# yamaHACK.net
KiCad netlist of a schematic drawn in EAGLE
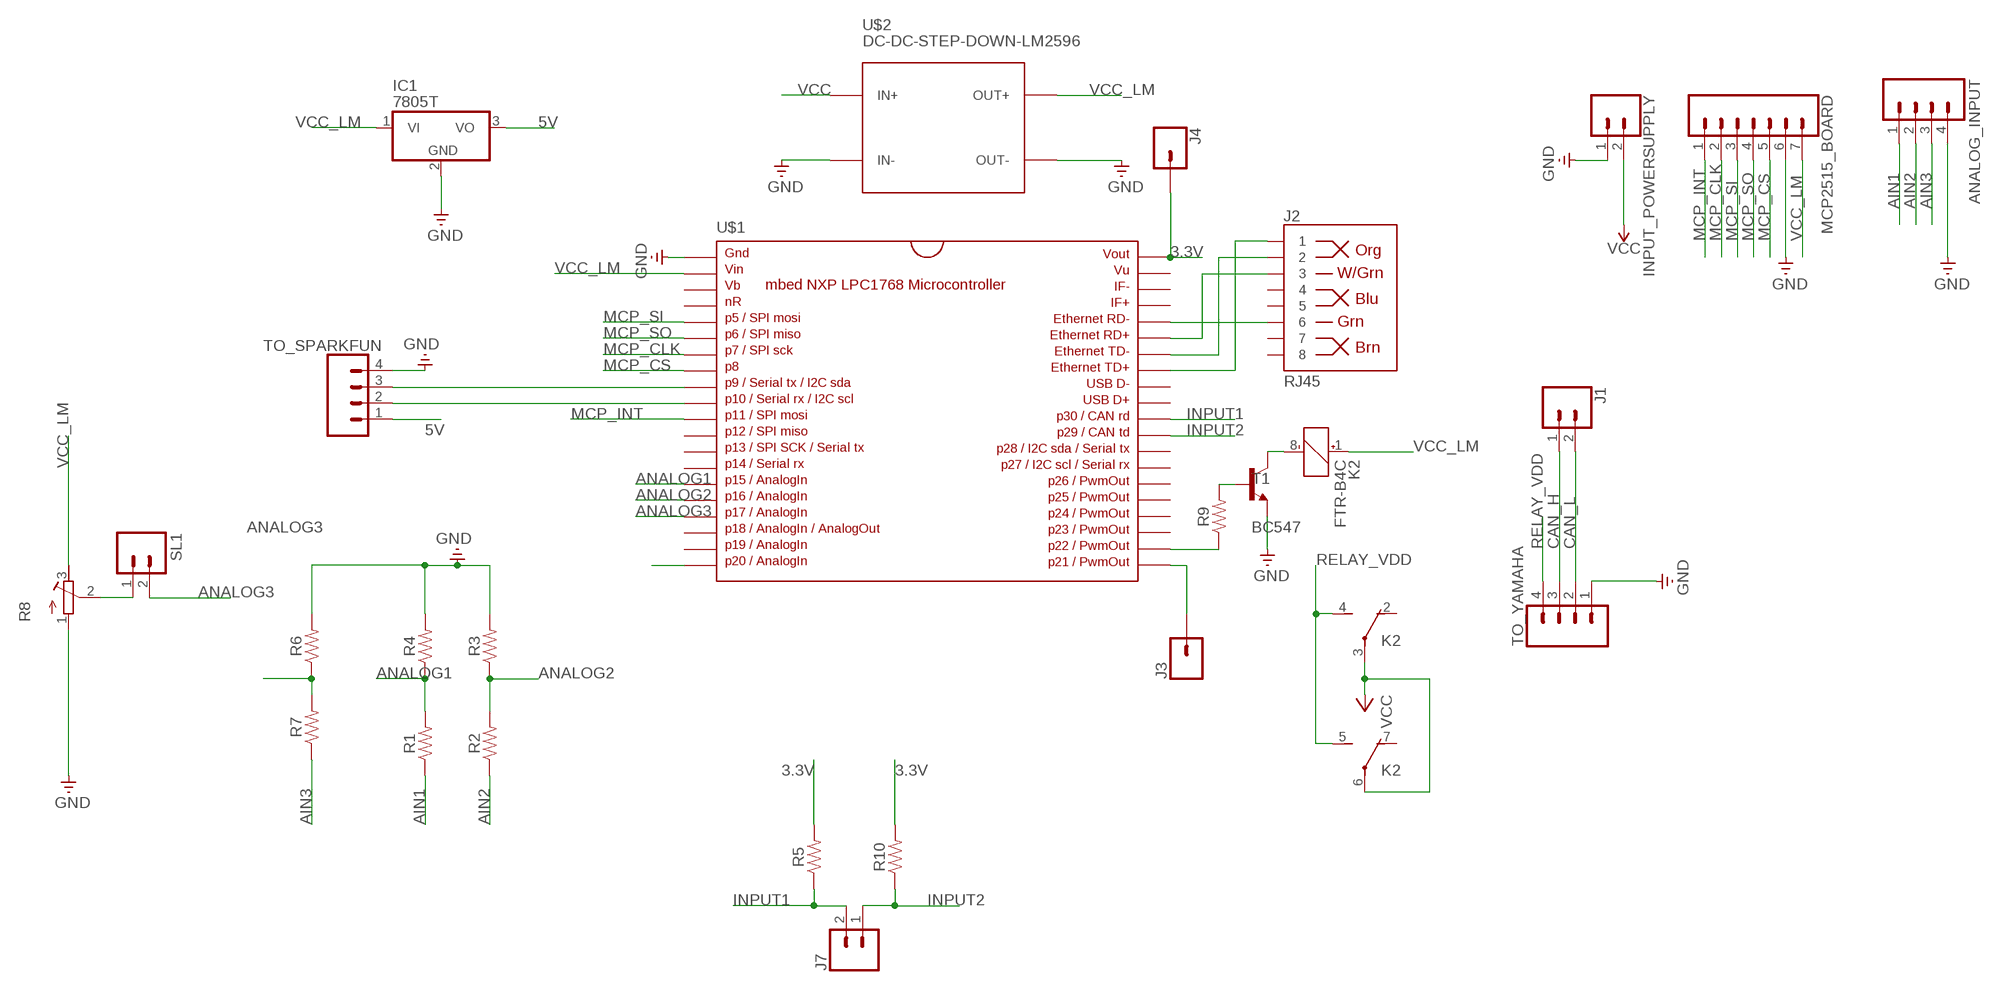
[diagram p0: schematic, sheet 1]

(export (version "E")
  (design (tool "Eeschema 10.0.6"))
  (components
    (comp (ref "ANALOG_INPUT")
      (value "M04")
      (footprint "eagle-import:04P")
      (libsource (lib "eagle-import") (part "M04"))
    )
    (comp (ref "IC1")
      (value "7805T")
      (footprint "eagle-import:TO220H")
      (libsource (lib "eagle-import") (part "78T05"))
    )
    (comp (ref "INPUT_POWERSUPPLY")
      (value "CONN_02PTH3")
      (footprint "eagle-import:1X02_LONGPADS")
      (libsource (lib "eagle-import") (part "CONN_02PTH3"))
    )
    (comp (ref "J1")
      (value "CONN_02")
      (footprint "eagle-import:1X02")
      (libsource (lib "eagle-import") (part "CONN_02"))
    )
    (comp (ref "J2")
      (value "RJ45")
      (footprint "eagle-import:RJ45-8")
      (libsource (lib "eagle-import") (part "RJ45-8"))
    )
    (comp (ref "J3")
      (value "CONN_01OFFSET")
      (footprint "eagle-import:1X01_OFFSET")
      (libsource (lib "eagle-import") (part "CONN_01OFFSET"))
    )
    (comp (ref "J4")
      (value "CONN_01OFFSET")
      (footprint "eagle-import:1X01_OFFSET")
      (libsource (lib "eagle-import") (part "CONN_01OFFSET"))
    )
    (comp (ref "J7")
      (value "CONN_02")
      (footprint "eagle-import:1X02")
      (libsource (lib "eagle-import") (part "CONN_02"))
    )
    (comp (ref "K2")
      (value "FTR-B4C")
      (footprint "eagle-import:FTR-B4C")
      (libsource (lib "eagle-import") (part "FTR-B4C"))
    )
    (comp (ref "MCP2515_BOARD")
      (value "CONN_07LONGPADS")
      (footprint "eagle-import:1X07_LONGPADS")
      (libsource (lib "eagle-import") (part "CONN_07LONGPADS"))
    )
    (comp (ref "R1")
      (value "RESISTORAXIAL-0.3")
      (footprint "eagle-import:AXIAL-0.3")
      (libsource (lib "eagle-import") (part "RESISTORAXIAL-0.3"))
    )
    (comp (ref "R2")
      (value "RESISTORAXIAL-0.3")
      (footprint "eagle-import:AXIAL-0.3")
      (libsource (lib "eagle-import") (part "RESISTORAXIAL-0.3"))
    )
    (comp (ref "R3")
      (value "RESISTORAXIAL-0.3")
      (footprint "eagle-import:AXIAL-0.3")
      (libsource (lib "eagle-import") (part "RESISTORAXIAL-0.3"))
    )
    (comp (ref "R4")
      (value "RESISTORAXIAL-0.3")
      (footprint "eagle-import:AXIAL-0.3")
      (libsource (lib "eagle-import") (part "RESISTORAXIAL-0.3"))
    )
    (comp (ref "R5")
      (value "RESISTORAXIAL-0.3")
      (footprint "eagle-import:AXIAL-0.3")
      (libsource (lib "eagle-import") (part "RESISTORAXIAL-0.3"))
    )
    (comp (ref "R6")
      (value "RESISTORAXIAL-0.3")
      (footprint "eagle-import:AXIAL-0.3")
      (libsource (lib "eagle-import") (part "RESISTORAXIAL-0.3"))
    )
    (comp (ref "R7")
      (value "RESISTORAXIAL-0.3")
      (footprint "eagle-import:AXIAL-0.3")
      (libsource (lib "eagle-import") (part "RESISTORAXIAL-0.3"))
    )
    (comp (ref "R8")
      (value "R-TRIMM3296W")
      (footprint "eagle-import:RTRIM3296W")
      (libsource (lib "eagle-import") (part "R-TRIMM3296W"))
    )
    (comp (ref "R9")
      (value "RESISTORAXIAL-0.3")
      (footprint "eagle-import:AXIAL-0.3")
      (libsource (lib "eagle-import") (part "RESISTORAXIAL-0.3"))
    )
    (comp (ref "R10")
      (value "RESISTORAXIAL-0.3")
      (footprint "eagle-import:AXIAL-0.3")
      (libsource (lib "eagle-import") (part "RESISTORAXIAL-0.3"))
    )
    (comp (ref "SL1")
      (value "M02")
      (footprint "eagle-import:02P")
      (libsource (lib "eagle-import") (part "M02"))
    )
    (comp (ref "T1")
      (value "BC547")
      (footprint "eagle-import:TO92")
      (libsource (lib "eagle-import") (part "BC547"))
    )
    (comp (ref "TO_SPARKFUN")
      (value "CONN_04")
      (footprint "eagle-import:1X04")
      (libsource (lib "eagle-import") (part "CONN_04"))
    )
    (comp (ref "TO_YAMAHA")
      (value "CONN_04")
      (footprint "eagle-import:1X04")
      (libsource (lib "eagle-import") (part "CONN_04"))
    )
    (comp (ref "U$1")
      (value "MBED1768")
      (footprint "eagle-import:DIL40_0.9")
      (libsource (lib "eagle-import") (part "MBED_NXP_LPC1768"))
    )
    (comp (ref "U$2")
      (value "DC-DC-STEP-DOWN-LM2596")
      (footprint "eagle-import:DC-DC-STEP-DOWN-LM2596")
      (libsource (lib "eagle-import") (part "DC-DC-STEP-DOWN-LM2596"))
    )
  )
  (nets
    (net (code "1") (name "/3.3V") (class "Default")
      (node (ref "J4") (pin "1") (pinfunction "1_1") (pintype "passive"))
      (node (ref "R10") (pin "P$2") (pinfunction "2_P$2") (pintype "passive"))
      (node (ref "R5") (pin "P$2") (pinfunction "2_P$2") (pintype "passive"))
      (node (ref "U$1") (pin "40") (pinfunction "P$40_40") (pintype "bidirectional"))
    )
    (net (code "2") (name "/5V") (class "Default")
      (node (ref "IC1") (pin "3") (pinfunction "VO_3") (pintype "passive"))
      (node (ref "TO_SPARKFUN") (pin "1") (pinfunction "1_1") (pintype "passive"))
    )
    (net (code "3") (name "/AIN1") (class "Default")
      (node (ref "ANALOG_INPUT") (pin "1") (pinfunction "1_1") (pintype "passive"))
      (node (ref "R1") (pin "P$1") (pinfunction "1_P$1") (pintype "passive"))
    )
    (net (code "4") (name "/AIN2") (class "Default")
      (node (ref "ANALOG_INPUT") (pin "2") (pinfunction "2_2") (pintype "passive"))
      (node (ref "R2") (pin "P$1") (pinfunction "1_P$1") (pintype "passive"))
    )
    (net (code "5") (name "/AIN3") (class "Default")
      (node (ref "ANALOG_INPUT") (pin "3") (pinfunction "3_3") (pintype "passive"))
      (node (ref "R7") (pin "P$1") (pinfunction "1_P$1") (pintype "passive"))
    )
    (net (code "6") (name "/ANALOG1") (class "Default")
      (node (ref "R1") (pin "P$2") (pinfunction "2_P$2") (pintype "passive"))
      (node (ref "R4") (pin "P$1") (pinfunction "1_P$1") (pintype "passive"))
      (node (ref "U$1") (pin "15") (pinfunction "P$15_15") (pintype "bidirectional"))
    )
    (net (code "7") (name "/ANALOG2") (class "Default")
      (node (ref "R2") (pin "P$2") (pinfunction "2_P$2") (pintype "passive"))
      (node (ref "R3") (pin "P$1") (pinfunction "1_P$1") (pintype "passive"))
      (node (ref "U$1") (pin "16") (pinfunction "P$16_16") (pintype "bidirectional"))
    )
    (net (code "8") (name "/ANALOG3") (class "Default")
      (node (ref "R6") (pin "P$1") (pinfunction "1_P$1") (pintype "passive"))
      (node (ref "R7") (pin "P$2") (pinfunction "2_P$2") (pintype "passive"))
      (node (ref "SL1") (pin "2") (pinfunction "2_2") (pintype "passive"))
      (node (ref "U$1") (pin "17") (pinfunction "P$17_17") (pintype "bidirectional"))
    )
    (net (code "9") (name "/CAN_H") (class "Default")
      (node (ref "J1") (pin "1") (pinfunction "1_1") (pintype "passive"))
      (node (ref "TO_YAMAHA") (pin "3") (pinfunction "3_3") (pintype "passive"))
    )
    (net (code "10") (name "/CAN_L") (class "Default")
      (node (ref "J1") (pin "2") (pinfunction "2_2") (pintype "passive"))
      (node (ref "TO_YAMAHA") (pin "2") (pinfunction "2_2") (pintype "passive"))
    )
    (net (code "11") (name "/INPUT1") (class "Default")
      (node (ref "J7") (pin "2") (pinfunction "2_2") (pintype "passive"))
      (node (ref "R5") (pin "P$1") (pinfunction "1_P$1") (pintype "passive"))
      (node (ref "U$1") (pin "30") (pinfunction "P$30_30") (pintype "bidirectional"))
    )
    (net (code "12") (name "/INPUT2") (class "Default")
      (node (ref "J7") (pin "1") (pinfunction "1_1") (pintype "passive"))
      (node (ref "R10") (pin "P$1") (pinfunction "1_P$1") (pintype "passive"))
      (node (ref "U$1") (pin "29") (pinfunction "P$29_29") (pintype "bidirectional"))
    )
    (net (code "13") (name "/MCP_CLK") (class "Default")
      (node (ref "MCP2515_BOARD") (pin "2") (pinfunction "2_2") (pintype "passive"))
      (node (ref "U$1") (pin "7") (pinfunction "P$7_7") (pintype "bidirectional"))
    )
    (net (code "14") (name "/MCP_CS") (class "Default")
      (node (ref "MCP2515_BOARD") (pin "5") (pinfunction "5_5") (pintype "passive"))
      (node (ref "U$1") (pin "8") (pinfunction "P$8_8") (pintype "bidirectional"))
    )
    (net (code "15") (name "/MCP_INT") (class "Default")
      (node (ref "MCP2515_BOARD") (pin "1") (pinfunction "1_1") (pintype "passive"))
      (node (ref "U$1") (pin "11") (pinfunction "P$11_11") (pintype "bidirectional"))
    )
    (net (code "16") (name "/MCP_SI") (class "Default")
      (node (ref "MCP2515_BOARD") (pin "3") (pinfunction "3_3") (pintype "passive"))
      (node (ref "U$1") (pin "5") (pinfunction "P$5_5") (pintype "bidirectional"))
    )
    (net (code "17") (name "/MCP_SO") (class "Default")
      (node (ref "MCP2515_BOARD") (pin "4") (pinfunction "4_4") (pintype "passive"))
      (node (ref "U$1") (pin "6") (pinfunction "P$6_6") (pintype "bidirectional"))
    )
    (net (code "18") (name "/RELAY_VDD") (class "Default")
      (node (ref "K2") (pin "4") (pinfunction "S_4") (pintype "passive"))
      (node (ref "K2") (pin "5") (pinfunction "S_5") (pintype "passive"))
      (node (ref "TO_YAMAHA") (pin "4") (pinfunction "4_4") (pintype "passive"))
    )
    (net (code "19") (name "/VCC_LM") (class "Default")
      (node (ref "IC1") (pin "1") (pinfunction "VI_1") (pintype "input"))
      (node (ref "K2") (pin "1") (pinfunction "+_1") (pintype "passive"))
      (node (ref "MCP2515_BOARD") (pin "7") (pinfunction "7_7") (pintype "passive"))
      (node (ref "R8") (pin "3") (pinfunction "E_3") (pintype "passive"))
      (node (ref "U$1") (pin "2") (pinfunction "P$2_2") (pintype "bidirectional"))
      (node (ref "U$2") (pin "OUT+") (pinfunction "OUT+_OUT+") (pintype "bidirectional"))
    )
    (net (code "20") (name "GND") (class "Default")
      (node (ref "ANALOG_INPUT") (pin "4") (pinfunction "4_4") (pintype "passive"))
      (node (ref "IC1") (pin "2") (pinfunction "GND_2") (pintype "passive"))
      (node (ref "INPUT_POWERSUPPLY") (pin "1") (pinfunction "1_1") (pintype "passive"))
      (node (ref "MCP2515_BOARD") (pin "6") (pinfunction "6_6") (pintype "passive"))
      (node (ref "R3") (pin "P$2") (pinfunction "2_P$2") (pintype "passive"))
      (node (ref "R4") (pin "P$2") (pinfunction "2_P$2") (pintype "passive"))
      (node (ref "R6") (pin "P$2") (pinfunction "2_P$2") (pintype "passive"))
      (node (ref "R8") (pin "1") (pinfunction "A_1") (pintype "passive"))
      (node (ref "T1") (pin "1") (pinfunction "E_1") (pintype "passive"))
      (node (ref "TO_SPARKFUN") (pin "4") (pinfunction "4_4") (pintype "passive"))
      (node (ref "TO_YAMAHA") (pin "1") (pinfunction "1_1") (pintype "passive"))
      (node (ref "U$1") (pin "1") (pinfunction "P$1_1") (pintype "bidirectional"))
      (node (ref "U$2") (pin "IN-") (pinfunction "IN-_IN-") (pintype "bidirectional"))
      (node (ref "U$2") (pin "OUT-") (pinfunction "OUT-_OUT-") (pintype "bidirectional"))
    )
    (net (code "21") (name "Net-(K2C--)") (class "Default")
      (node (ref "K2") (pin "8") (pinfunction "-_8") (pintype "passive"))
      (node (ref "T1") (pin "3") (pinfunction "C_3") (pintype "passive"))
    )
    (net (code "22") (name "Net-(R8-S)") (class "Default")
      (node (ref "R8") (pin "2") (pinfunction "S_2") (pintype "passive"))
      (node (ref "SL1") (pin "1") (pinfunction "1_1") (pintype "passive"))
    )
    (net (code "23") (name "Net-(R9-1)") (class "Default")
      (node (ref "R9") (pin "P$1") (pinfunction "1_P$1") (pintype "passive"))
      (node (ref "U$1") (pin "22") (pinfunction "P$22_22") (pintype "bidirectional"))
    )
    (net (code "24") (name "Net-(R9-2)") (class "Default")
      (node (ref "R9") (pin "P$2") (pinfunction "2_P$2") (pintype "passive"))
      (node (ref "T1") (pin "2") (pinfunction "B_2") (pintype "passive"))
    )
    (net (code "25") (name "Net-(U$1-P$9)") (class "Default")
      (node (ref "TO_SPARKFUN") (pin "3") (pinfunction "3_3") (pintype "passive"))
      (node (ref "U$1") (pin "9") (pinfunction "P$9_9") (pintype "bidirectional"))
    )
    (net (code "26") (name "Net-(U$1-P$10)") (class "Default")
      (node (ref "TO_SPARKFUN") (pin "2") (pinfunction "2_2") (pintype "passive"))
      (node (ref "U$1") (pin "10") (pinfunction "P$10_10") (pintype "bidirectional"))
    )
    (net (code "27") (name "Net-(U$1-P$21)") (class "Default")
      (node (ref "J3") (pin "1") (pinfunction "1_1") (pintype "passive"))
      (node (ref "U$1") (pin "21") (pinfunction "P$21_21") (pintype "bidirectional"))
    )
    (net (code "28") (name "Net-(U$1-P$33)") (class "Default")
      (node (ref "J2") (pin "1") (pinfunction "1_1") (pintype "bidirectional"))
      (node (ref "U$1") (pin "33") (pinfunction "P$33_33") (pintype "bidirectional"))
    )
    (net (code "29") (name "Net-(U$1-P$34)") (class "Default")
      (node (ref "J2") (pin "2") (pinfunction "2_2") (pintype "bidirectional"))
      (node (ref "U$1") (pin "34") (pinfunction "P$34_34") (pintype "bidirectional"))
    )
    (net (code "30") (name "Net-(U$1-P$35)") (class "Default")
      (node (ref "J2") (pin "3") (pinfunction "3_3") (pintype "bidirectional"))
      (node (ref "U$1") (pin "35") (pinfunction "P$35_35") (pintype "bidirectional"))
    )
    (net (code "31") (name "Net-(U$1-P$36)") (class "Default")
      (node (ref "J2") (pin "6") (pinfunction "6_6") (pintype "bidirectional"))
      (node (ref "U$1") (pin "36") (pinfunction "P$36_36") (pintype "bidirectional"))
    )
    (net (code "32") (name "VCC") (class "Default")
      (node (ref "INPUT_POWERSUPPLY") (pin "2") (pinfunction "2_2") (pintype "passive"))
      (node (ref "K2") (pin "3") (pinfunction "P_3") (pintype "passive"))
      (node (ref "K2") (pin "6") (pinfunction "P_6") (pintype "passive"))
      (node (ref "U$2") (pin "IN+") (pinfunction "IN+_IN+") (pintype "bidirectional"))
    )
    (net (code "33") (name "unconnected-(J2-Pad4)") (class "Default")
      (node (ref "J2") (pin "4") (pinfunction "4_4") (pintype "bidirectional"))
    )
    (net (code "34") (name "unconnected-(J2-Pad5)") (class "Default")
      (node (ref "J2") (pin "5") (pinfunction "5_5") (pintype "bidirectional"))
    )
    (net (code "35") (name "unconnected-(J2-Pad7)") (class "Default")
      (node (ref "J2") (pin "7") (pinfunction "7_7") (pintype "bidirectional"))
    )
    (net (code "36") (name "unconnected-(J2-Pad8)") (class "Default")
      (node (ref "J2") (pin "8") (pinfunction "8_8") (pintype "bidirectional"))
    )
    (net (code "37") (name "unconnected-(K2A-O-Pad2)") (class "Default")
      (node (ref "K2") (pin "2") (pinfunction "O_2") (pintype "passive"))
    )
    (net (code "38") (name "unconnected-(K2B-O-Pad7)") (class "Default")
      (node (ref "K2") (pin "7") (pinfunction "O_7") (pintype "passive"))
    )
    (net (code "39") (name "unconnected-(U$1-P$3-Pad3)") (class "Default")
      (node (ref "U$1") (pin "3") (pinfunction "P$3_3") (pintype "bidirectional"))
    )
    (net (code "40") (name "unconnected-(U$1-P$4-Pad4)") (class "Default")
      (node (ref "U$1") (pin "4") (pinfunction "P$4_4") (pintype "bidirectional"))
    )
    (net (code "41") (name "unconnected-(U$1-P$12-Pad12)") (class "Default")
      (node (ref "U$1") (pin "12") (pinfunction "P$12_12") (pintype "bidirectional"))
    )
    (net (code "42") (name "unconnected-(U$1-P$13-Pad13)") (class "Default")
      (node (ref "U$1") (pin "13") (pinfunction "P$13_13") (pintype "bidirectional"))
    )
    (net (code "43") (name "unconnected-(U$1-P$14-Pad14)") (class "Default")
      (node (ref "U$1") (pin "14") (pinfunction "P$14_14") (pintype "bidirectional"))
    )
    (net (code "44") (name "unconnected-(U$1-P$18-Pad18)") (class "Default")
      (node (ref "U$1") (pin "18") (pinfunction "P$18_18") (pintype "bidirectional"))
    )
    (net (code "45") (name "unconnected-(U$1-P$19-Pad19)") (class "Default")
      (node (ref "U$1") (pin "19") (pinfunction "P$19_19") (pintype "bidirectional"))
    )
    (net (code "46") (name "unconnected-(U$1-P$20-Pad20)") (class "Default")
      (node (ref "U$1") (pin "20") (pinfunction "P$20_20") (pintype "bidirectional"))
    )
    (net (code "47") (name "unconnected-(U$1-P$23-Pad23)") (class "Default")
      (node (ref "U$1") (pin "23") (pinfunction "P$23_23") (pintype "bidirectional"))
    )
    (net (code "48") (name "unconnected-(U$1-P$24-Pad24)") (class "Default")
      (node (ref "U$1") (pin "24") (pinfunction "P$24_24") (pintype "bidirectional"))
    )
    (net (code "49") (name "unconnected-(U$1-P$25-Pad25)") (class "Default")
      (node (ref "U$1") (pin "25") (pinfunction "P$25_25") (pintype "bidirectional"))
    )
    (net (code "50") (name "unconnected-(U$1-P$26-Pad26)") (class "Default")
      (node (ref "U$1") (pin "26") (pinfunction "P$26_26") (pintype "bidirectional"))
    )
    (net (code "51") (name "unconnected-(U$1-P$27-Pad27)") (class "Default")
      (node (ref "U$1") (pin "27") (pinfunction "P$27_27") (pintype "bidirectional"))
    )
    (net (code "52") (name "unconnected-(U$1-P$28-Pad28)") (class "Default")
      (node (ref "U$1") (pin "28") (pinfunction "P$28_28") (pintype "bidirectional"))
    )
    (net (code "53") (name "unconnected-(U$1-P$31-Pad31)") (class "Default")
      (node (ref "U$1") (pin "31") (pinfunction "P$31_31") (pintype "bidirectional"))
    )
    (net (code "54") (name "unconnected-(U$1-P$32-Pad32)") (class "Default")
      (node (ref "U$1") (pin "32") (pinfunction "P$32_32") (pintype "bidirectional"))
    )
    (net (code "55") (name "unconnected-(U$1-P$37-Pad37)") (class "Default")
      (node (ref "U$1") (pin "37") (pinfunction "P$37_37") (pintype "bidirectional"))
    )
    (net (code "56") (name "unconnected-(U$1-P$38-Pad38)") (class "Default")
      (node (ref "U$1") (pin "38") (pinfunction "P$38_38") (pintype "bidirectional"))
    )
    (net (code "57") (name "unconnected-(U$1-P$39-Pad39)") (class "Default")
      (node (ref "U$1") (pin "39") (pinfunction "P$39_39") (pintype "bidirectional"))
    )
  )
)
